# Leak2.net
KiCad netlist of a schematic drawn in EAGLE
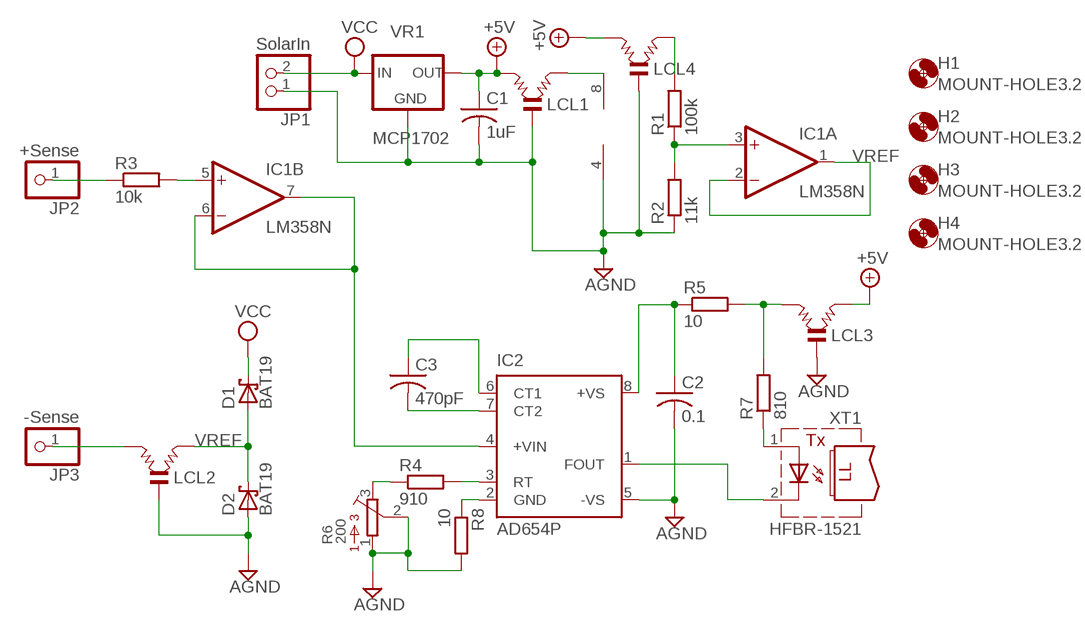
[diagram p0: schematic, sheet 1]

(export (version "E")
  (design (tool "Eeschema 10.0.6"))
  (components
    (comp (ref "C1")
      (value "1uF")
      (footprint "eagle-import:C050-035X075")
      (libsource (lib "eagle-import") (part "C-US050-035X075"))
    )
    (comp (ref "C2")
      (value "0.1")
      (footprint "eagle-import:C050-035X075")
      (libsource (lib "eagle-import") (part "C-US050-035X075"))
    )
    (comp (ref "C3")
      (value "470pF")
      (footprint "eagle-import:C050-035X075")
      (libsource (lib "eagle-import") (part "C-US050-035X075"))
    )
    (comp (ref "D1")
      (value "BAT19")
      (footprint "eagle-import:DO35-10")
      (libsource (lib "eagle-import") (part "BAT19"))
    )
    (comp (ref "D2")
      (value "BAT19")
      (footprint "eagle-import:DO35-10")
      (libsource (lib "eagle-import") (part "BAT19"))
    )
    (comp (ref "H1")
      (value "MOUNT-HOLE3.2")
      (footprint "eagle-import:3,2")
      (libsource (lib "eagle-import") (part "MOUNT-HOLE3.2"))
    )
    (comp (ref "H2")
      (value "MOUNT-HOLE3.2")
      (footprint "eagle-import:3,2")
      (libsource (lib "eagle-import") (part "MOUNT-HOLE3.2"))
    )
    (comp (ref "H3")
      (value "MOUNT-HOLE3.2")
      (footprint "eagle-import:3,2")
      (libsource (lib "eagle-import") (part "MOUNT-HOLE3.2"))
    )
    (comp (ref "H4")
      (value "MOUNT-HOLE3.2")
      (footprint "eagle-import:3,2")
      (libsource (lib "eagle-import") (part "MOUNT-HOLE3.2"))
    )
    (comp (ref "IC1")
      (value "LM358N")
      (footprint "eagle-import:DIL08")
      (libsource (lib "eagle-import") (part "LM358N"))
    )
    (comp (ref "IC2")
      (value "AD654P")
      (footprint "eagle-import:DIL08")
      (libsource (lib "eagle-import") (part "AD654P"))
    )
    (comp (ref "JP1")
      (value "SolarIn")
      (footprint "eagle-import:1X02")
      (libsource (lib "eagle-import") (part "PINHD-1X2"))
    )
    (comp (ref "JP2")
      (value "+Sense")
      (footprint "eagle-import:1X01")
      (libsource (lib "eagle-import") (part "PINHD-1X1"))
    )
    (comp (ref "JP3")
      (value "-Sense")
      (footprint "eagle-import:1X01")
      (libsource (lib "eagle-import") (part "PINHD-1X1"))
    )
    (comp (ref "LCL1")
      (value "LCL")
      (footprint "eagle-import:LCL")
      (libsource (lib "eagle-import") (part "LCL"))
    )
    (comp (ref "LCL2")
      (value "LCL")
      (footprint "eagle-import:LCL")
      (libsource (lib "eagle-import") (part "LCL"))
    )
    (comp (ref "LCL3")
      (value "LCL")
      (footprint "eagle-import:LCL")
      (libsource (lib "eagle-import") (part "LCL"))
    )
    (comp (ref "LCL4")
      (value "LCL")
      (footprint "eagle-import:LCL")
      (libsource (lib "eagle-import") (part "LCL"))
    )
    (comp (ref "R1")
      (value "100k")
      (footprint "eagle-import:0204_7")
      (libsource (lib "eagle-import") (part "R-EU_0204/7"))
    )
    (comp (ref "R2")
      (value "11k")
      (footprint "eagle-import:0204_7")
      (libsource (lib "eagle-import") (part "R-EU_0204/7"))
    )
    (comp (ref "R3")
      (value "10k")
      (footprint "eagle-import:0204_7")
      (libsource (lib "eagle-import") (part "R-EU_0204/7"))
    )
    (comp (ref "R4")
      (value "910")
      (footprint "eagle-import:0204_7")
      (libsource (lib "eagle-import") (part "R-EU_0204/7"))
    )
    (comp (ref "R5")
      (value "10")
      (footprint "eagle-import:0204_7")
      (libsource (lib "eagle-import") (part "R-EU_0204/7"))
    )
    (comp (ref "R6")
      (value "200")
      (footprint "eagle-import:3386F")
      (libsource (lib "eagle-import") (part "3386-F"))
    )
    (comp (ref "R7")
      (value "810")
      (footprint "eagle-import:0204_7")
      (libsource (lib "eagle-import") (part "R-EU_0204/7"))
    )
    (comp (ref "R8")
      (value "10")
      (footprint "eagle-import:0204_7")
      (libsource (lib "eagle-import") (part "R-EU_0204/7"))
    )
    (comp (ref "VR1")
      (value "MCP1702")
      (footprint "eagle-import:TO92-")
      (libsource (lib "eagle-import") (part "MCP1702"))
    )
    (comp (ref "XT1")
      (value "HFBR-1521")
      (footprint "eagle-import:HFBR-15X3")
      (libsource (lib "eagle-import") (part "HFBR-1521"))
    )
  )
  (nets
    (net (code "1") (name "+5V") (class "Default")
      (node (ref "C1") (pin "1") (pinfunction "1_1") (pintype "passive"))
      (node (ref "LCL1") (pin "1") (pinfunction "1_1") (pintype "passive"))
      (node (ref "LCL3") (pin "2") (pinfunction "2_2") (pintype "passive"))
      (node (ref "LCL4") (pin "1") (pinfunction "1_1") (pintype "passive"))
      (node (ref "VR1") (pin "1") (pinfunction "OUT_1") (pintype "passive"))
    )
    (net (code "2") (name "/VREF") (class "Default")
      (node (ref "D1") (pin "A") (pinfunction "A_A") (pintype "passive"))
      (node (ref "D2") (pin "C") (pinfunction "C_C") (pintype "passive"))
      (node (ref "IC1") (pin "1") (pinfunction "OUT_1") (pintype "output"))
      (node (ref "IC1") (pin "2") (pinfunction "-IN_2") (pintype "input"))
      (node (ref "LCL2") (pin "2") (pinfunction "2_2") (pintype "passive"))
    )
    (net (code "3") (name "AGND") (class "Default")
      (node (ref "C1") (pin "2") (pinfunction "2_2") (pintype "passive"))
      (node (ref "C2") (pin "2") (pinfunction "2_2") (pintype "passive"))
      (node (ref "D2") (pin "A") (pinfunction "A_A") (pintype "passive"))
      (node (ref "IC1") (pin "4") (pinfunction "V-_4") (pintype "power_in"))
      (node (ref "IC2") (pin "5") (pinfunction "-VS_5") (pintype "power_in"))
      (node (ref "JP1") (pin "1") (pinfunction "1_1") (pintype "passive"))
      (node (ref "LCL1") (pin "0") (pinfunction "GND_0") (pintype "power_in"))
      (node (ref "LCL2") (pin "0") (pinfunction "GND_0") (pintype "power_in"))
      (node (ref "LCL3") (pin "0") (pinfunction "GND_0") (pintype "power_in"))
      (node (ref "LCL4") (pin "0") (pinfunction "GND_0") (pintype "power_in"))
      (node (ref "R2") (pin "1") (pinfunction "1_1") (pintype "passive"))
      (node (ref "R6") (pin "1") (pinfunction "1_1") (pintype "passive"))
      (node (ref "R6") (pin "2") (pinfunction "2_2") (pintype "passive"))
      (node (ref "R8") (pin "2") (pinfunction "2_2") (pintype "passive"))
      (node (ref "VR1") (pin "3") (pinfunction "GND_3") (pintype "input"))
    )
    (net (code "4") (name "Net-(IC1A-+IN)") (class "Default")
      (node (ref "IC1") (pin "3") (pinfunction "+IN_3") (pintype "input"))
      (node (ref "R1") (pin "1") (pinfunction "1_1") (pintype "passive"))
      (node (ref "R2") (pin "2") (pinfunction "2_2") (pintype "passive"))
    )
    (net (code "5") (name "Net-(IC1B-+IN)") (class "Default")
      (node (ref "IC1") (pin "5") (pinfunction "+IN_5") (pintype "input"))
      (node (ref "R3") (pin "2") (pinfunction "2_2") (pintype "passive"))
    )
    (net (code "6") (name "Net-(IC1B--IN)") (class "Default")
      (node (ref "IC1") (pin "6") (pinfunction "-IN_6") (pintype "input"))
      (node (ref "IC1") (pin "7") (pinfunction "OUT_7") (pintype "output"))
      (node (ref "IC2") (pin "4") (pinfunction "+VIN_4") (pintype "input"))
    )
    (net (code "7") (name "Net-(IC1C-V+)") (class "Default")
      (node (ref "IC1") (pin "8") (pinfunction "V+_8") (pintype "power_in"))
      (node (ref "LCL1") (pin "2") (pinfunction "2_2") (pintype "passive"))
    )
    (net (code "8") (name "Net-(IC2-+VS)") (class "Default")
      (node (ref "C2") (pin "1") (pinfunction "1_1") (pintype "passive"))
      (node (ref "IC2") (pin "8") (pinfunction "+VS_8") (pintype "power_in"))
      (node (ref "R5") (pin "1") (pinfunction "1_1") (pintype "passive"))
    )
    (net (code "9") (name "Net-(IC2-CT1)") (class "Default")
      (node (ref "C3") (pin "1") (pinfunction "1_1") (pintype "passive"))
      (node (ref "IC2") (pin "6") (pinfunction "CT1_6") (pintype "passive"))
    )
    (net (code "10") (name "Net-(IC2-CT2)") (class "Default")
      (node (ref "C3") (pin "2") (pinfunction "2_2") (pintype "passive"))
      (node (ref "IC2") (pin "7") (pinfunction "CT2_7") (pintype "passive"))
    )
    (net (code "11") (name "Net-(IC2-FOUT)") (class "Default")
      (node (ref "IC2") (pin "1") (pinfunction "FOUT_1") (pintype "open_collector"))
      (node (ref "XT1") (pin "2") (pinfunction "C_2") (pintype "passive"))
    )
    (net (code "12") (name "Net-(IC2-GND)") (class "Default")
      (node (ref "IC2") (pin "2") (pinfunction "GND_2") (pintype "power_in"))
      (node (ref "R8") (pin "1") (pinfunction "1_1") (pintype "passive"))
    )
    (net (code "13") (name "Net-(IC2-RT)") (class "Default")
      (node (ref "IC2") (pin "3") (pinfunction "RT_3") (pintype "passive"))
      (node (ref "R4") (pin "2") (pinfunction "2_2") (pintype "passive"))
    )
    (net (code "14") (name "Net-(JP2-Pad1)") (class "Default")
      (node (ref "JP2") (pin "1") (pinfunction "1_1") (pintype "passive"))
      (node (ref "R3") (pin "1") (pinfunction "1_1") (pintype "passive"))
    )
    (net (code "15") (name "Net-(JP3-Pad1)") (class "Default")
      (node (ref "JP3") (pin "1") (pinfunction "1_1") (pintype "passive"))
      (node (ref "LCL2") (pin "1") (pinfunction "1_1") (pintype "passive"))
    )
    (net (code "16") (name "Net-(LCL3-Pad1)") (class "Default")
      (node (ref "LCL3") (pin "1") (pinfunction "1_1") (pintype "passive"))
      (node (ref "R5") (pin "2") (pinfunction "2_2") (pintype "passive"))
      (node (ref "R7") (pin "2") (pinfunction "2_2") (pintype "passive"))
    )
    (net (code "17") (name "Net-(LCL4-Pad2)") (class "Default")
      (node (ref "LCL4") (pin "2") (pinfunction "2_2") (pintype "passive"))
      (node (ref "R1") (pin "2") (pinfunction "2_2") (pintype "passive"))
    )
    (net (code "18") (name "Net-(R4-Pad1)") (class "Default")
      (node (ref "R4") (pin "1") (pinfunction "1_1") (pintype "passive"))
      (node (ref "R6") (pin "3") (pinfunction "3_3") (pintype "passive"))
    )
    (net (code "19") (name "Net-(XT1-A)") (class "Default")
      (node (ref "R7") (pin "1") (pinfunction "1_1") (pintype "passive"))
      (node (ref "XT1") (pin "1") (pinfunction "A_1") (pintype "passive"))
    )
    (net (code "20") (name "VCC") (class "Default")
      (node (ref "D1") (pin "C") (pinfunction "C_C") (pintype "passive"))
      (node (ref "JP1") (pin "2") (pinfunction "2_2") (pintype "passive"))
      (node (ref "VR1") (pin "2") (pinfunction "IN_2") (pintype "input"))
    )
  )
)
